# LIDO-HW_100_RearConnector.net
KiCad netlist of a schematic drawn in Altium Designer
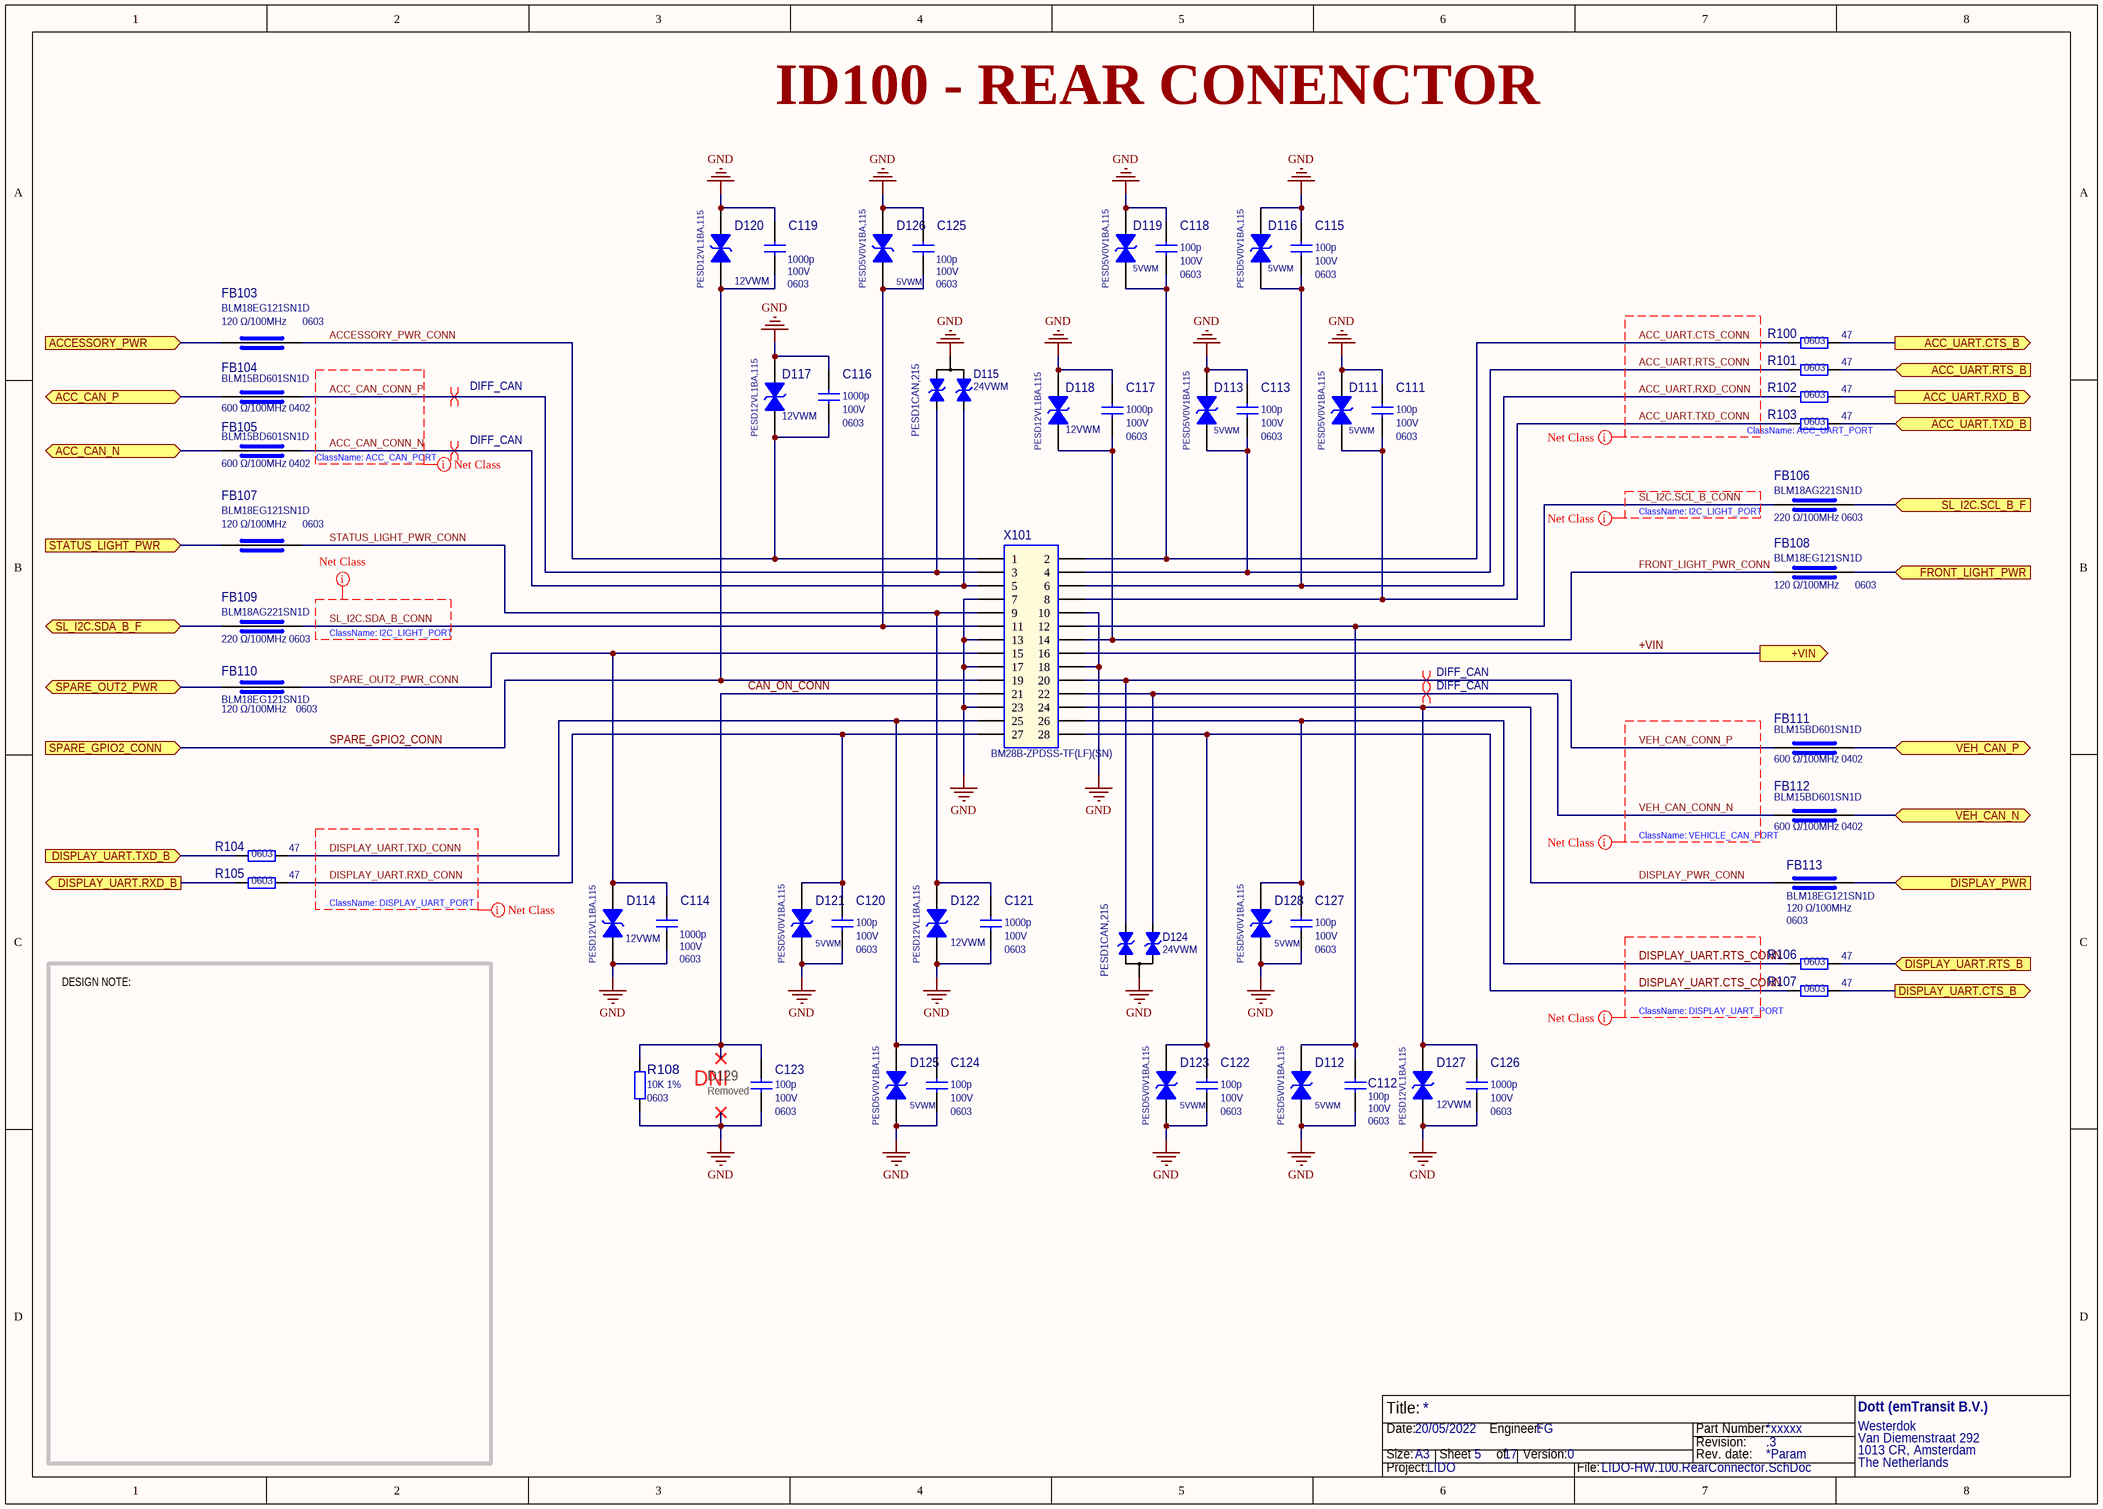
[diagram p0: LIDO-HW.100.RearConnector.SchDoc]

(export (version "E")
  (design (tool "Eeschema 10.0.6"))
  (components
    (comp (ref "C111")
      (value "100p")
      (footprint "CAP_0603_1608X90-N_MURATA_A")
      (description "CAP CER 100PF 100V C0G 0603")
      (fields
        (field (name "MANUFACTURER PART NUMBER") "CGA3E2C0G2A101J080AA")
        (field (name "MANUFACTURER") "TDK Corporation")
        (field (name "PART VALUE") "100p")
        (field (name "PART VALUE 2") "100V")
        (field (name "PART PACKAGE") "0603")
      )
      (libsource (lib "DB_Library") (part "Ceramic"))
    )
    (comp (ref "C112")
      (value "100p")
      (footprint "CAP_0603_1608X90-N_MURATA_A")
      (description "CAP CER 100PF 100V C0G 0603")
      (fields
        (field (name "MANUFACTURER PART NUMBER") "CGA3E2C0G2A101J080AA")
        (field (name "MANUFACTURER") "TDK Corporation")
        (field (name "PART VALUE") "100p")
        (field (name "PART VALUE 2") "100V")
        (field (name "PART PACKAGE") "0603")
      )
      (libsource (lib "DB_Library") (part "Ceramic"))
    )
    (comp (ref "C113")
      (value "100p")
      (footprint "CAP_0603_1608X90-N_MURATA_A")
      (description "CAP CER 100PF 100V C0G 0603")
      (fields
        (field (name "MANUFACTURER PART NUMBER") "CGA3E2C0G2A101J080AA")
        (field (name "MANUFACTURER") "TDK Corporation")
        (field (name "PART VALUE") "100p")
        (field (name "PART VALUE 2") "100V")
        (field (name "PART PACKAGE") "0603")
      )
      (libsource (lib "DB_Library") (part "Ceramic"))
    )
    (comp (ref "C114")
      (value "1000p")
      (footprint "CAP_0603_1608X90-N_MURATA_A")
      (description "CAP CER 1000PF 100V X7R 0603")
      (fields
        (field (name "MANUFACTURER PART NUMBER") "CGA3E2X7R2A102K080AA")
        (field (name "MANUFACTURER") "TDK Corporation")
        (field (name "PART VALUE") "1000p")
        (field (name "PART VALUE 2") "100V")
        (field (name "PART PACKAGE") "0603")
      )
      (libsource (lib "DB_Library") (part "Ceramic"))
    )
    (comp (ref "C115")
      (value "100p")
      (footprint "CAP_0603_1608X90-N_MURATA_A")
      (description "CAP CER 100PF 100V C0G 0603")
      (fields
        (field (name "MANUFACTURER PART NUMBER") "CGA3E2C0G2A101J080AA")
        (field (name "MANUFACTURER") "TDK Corporation")
        (field (name "PART VALUE") "100p")
        (field (name "PART VALUE 2") "100V")
        (field (name "PART PACKAGE") "0603")
      )
      (libsource (lib "DB_Library") (part "Ceramic"))
    )
    (comp (ref "C116")
      (value "1000p")
      (footprint "CAP_0603_1608X90-N_MURATA_A")
      (description "CAP CER 1000PF 100V X7R 0603")
      (fields
        (field (name "MANUFACTURER PART NUMBER") "CGA3E2X7R2A102K080AA")
        (field (name "MANUFACTURER") "TDK Corporation")
        (field (name "PART VALUE") "1000p")
        (field (name "PART VALUE 2") "100V")
        (field (name "PART PACKAGE") "0603")
      )
      (libsource (lib "DB_Library") (part "Ceramic"))
    )
    (comp (ref "C117")
      (value "1000p")
      (footprint "CAP_0603_1608X90-N_MURATA_A")
      (description "CAP CER 1000PF 100V X7R 0603")
      (fields
        (field (name "MANUFACTURER PART NUMBER") "CGA3E2X7R2A102K080AA")
        (field (name "MANUFACTURER") "TDK Corporation")
        (field (name "PART VALUE") "1000p")
        (field (name "PART VALUE 2") "100V")
        (field (name "PART PACKAGE") "0603")
      )
      (libsource (lib "DB_Library") (part "Ceramic"))
    )
    (comp (ref "C118")
      (value "100p")
      (footprint "CAP_0603_1608X90-N_MURATA_A")
      (description "CAP CER 100PF 100V C0G 0603")
      (fields
        (field (name "MANUFACTURER PART NUMBER") "CGA3E2C0G2A101J080AA")
        (field (name "MANUFACTURER") "TDK Corporation")
        (field (name "PART VALUE") "100p")
        (field (name "PART VALUE 2") "100V")
        (field (name "PART PACKAGE") "0603")
      )
      (libsource (lib "DB_Library") (part "Ceramic"))
    )
    (comp (ref "C119")
      (value "1000p")
      (footprint "CAP_0603_1608X90-N_MURATA_A")
      (description "CAP CER 1000PF 100V X7R 0603")
      (fields
        (field (name "MANUFACTURER PART NUMBER") "CGA3E2X7R2A102K080AA")
        (field (name "MANUFACTURER") "TDK Corporation")
        (field (name "PART VALUE") "1000p")
        (field (name "PART VALUE 2") "100V")
        (field (name "PART PACKAGE") "0603")
      )
      (libsource (lib "DB_Library") (part "Ceramic"))
    )
    (comp (ref "C120")
      (value "100p")
      (footprint "CAP_0603_1608X90-N_MURATA_A")
      (description "CAP CER 100PF 100V C0G 0603")
      (fields
        (field (name "MANUFACTURER PART NUMBER") "CGA3E2C0G2A101J080AA")
        (field (name "MANUFACTURER") "TDK Corporation")
        (field (name "PART VALUE") "100p")
        (field (name "PART VALUE 2") "100V")
        (field (name "PART PACKAGE") "0603")
      )
      (libsource (lib "DB_Library") (part "Ceramic"))
    )
    (comp (ref "C121")
      (value "1000p")
      (footprint "CAP_0603_1608X90-N_MURATA_A")
      (description "CAP CER 1000PF 100V X7R 0603")
      (fields
        (field (name "MANUFACTURER PART NUMBER") "CGA3E2X7R2A102K080AA")
        (field (name "MANUFACTURER") "TDK Corporation")
        (field (name "PART VALUE") "1000p")
        (field (name "PART VALUE 2") "100V")
        (field (name "PART PACKAGE") "0603")
      )
      (libsource (lib "DB_Library") (part "Ceramic"))
    )
    (comp (ref "C122")
      (value "100p")
      (footprint "CAP_0603_1608X90-N_MURATA_A")
      (description "CAP CER 100PF 100V C0G 0603")
      (fields
        (field (name "MANUFACTURER PART NUMBER") "CGA3E2C0G2A101J080AA")
        (field (name "MANUFACTURER") "TDK Corporation")
        (field (name "PART VALUE") "100p")
        (field (name "PART VALUE 2") "100V")
        (field (name "PART PACKAGE") "0603")
      )
      (libsource (lib "DB_Library") (part "Ceramic"))
    )
    (comp (ref "C123")
      (value "100p")
      (footprint "CAP_0603_1608X90-N_MURATA_A")
      (description "CAP CER 100PF 100V C0G 0603")
      (fields
        (field (name "MANUFACTURER PART NUMBER") "CGA3E2C0G2A101J080AA")
        (field (name "MANUFACTURER") "TDK Corporation")
        (field (name "PART VALUE") "100p")
        (field (name "PART VALUE 2") "100V")
        (field (name "PART PACKAGE") "0603")
      )
      (libsource (lib "DB_Library") (part "Ceramic"))
    )
    (comp (ref "C124")
      (value "100p")
      (footprint "CAP_0603_1608X90-N_MURATA_A")
      (description "CAP CER 100PF 100V C0G 0603")
      (fields
        (field (name "MANUFACTURER PART NUMBER") "CGA3E2C0G2A101J080AA")
        (field (name "MANUFACTURER") "TDK Corporation")
        (field (name "PART VALUE") "100p")
        (field (name "PART VALUE 2") "100V")
        (field (name "PART PACKAGE") "0603")
      )
      (libsource (lib "DB_Library") (part "Ceramic"))
    )
    (comp (ref "C125")
      (value "100p")
      (footprint "CAP_0603_1608X90-N_MURATA_A")
      (description "CAP CER 100PF 100V C0G 0603")
      (fields
        (field (name "MANUFACTURER PART NUMBER") "CGA3E2C0G2A101J080AA")
        (field (name "MANUFACTURER") "TDK Corporation")
        (field (name "PART VALUE") "100p")
        (field (name "PART VALUE 2") "100V")
        (field (name "PART PACKAGE") "0603")
      )
      (libsource (lib "DB_Library") (part "Ceramic"))
    )
    (comp (ref "C126")
      (value "1000p")
      (footprint "CAP_0603_1608X90-N_MURATA_A")
      (description "CAP CER 1000PF 100V X7R 0603")
      (fields
        (field (name "MANUFACTURER PART NUMBER") "CGA3E2X7R2A102K080AA")
        (field (name "MANUFACTURER") "TDK Corporation")
        (field (name "PART VALUE") "1000p")
        (field (name "PART VALUE 2") "100V")
        (field (name "PART PACKAGE") "0603")
      )
      (libsource (lib "DB_Library") (part "Ceramic"))
    )
    (comp (ref "C127")
      (value "100p")
      (footprint "CAP_0603_1608X90-N_MURATA_A")
      (description "CAP CER 100PF 100V C0G 0603")
      (fields
        (field (name "MANUFACTURER PART NUMBER") "CGA3E2C0G2A101J080AA")
        (field (name "MANUFACTURER") "TDK Corporation")
        (field (name "PART VALUE") "100p")
        (field (name "PART VALUE 2") "100V")
        (field (name "PART PACKAGE") "0603")
      )
      (libsource (lib "DB_Library") (part "Ceramic"))
    )
    (comp (ref "D111")
      (value "5VWM")
      (footprint "NXP_SOD-323_250X125X95L30x32_A")
      (description "12.5V Clamp 4.8A (8/20µs) Ipp Tvs Diode Surface Mount SOD-323")
      (fields
        (field (name "MANUFACTURER PART NUMBER") "PESD5V0V1BA,115")
        (field (name "MANUFACTURER") "Nexperia USA Inc.")
        (field (name "PART VALUE") "5VWM")
        (field (name "OBSOLETE PART") "False")
      )
      (libsource (lib "DB_Library") (part "BI-TVS_DIODE_B"))
    )
    (comp (ref "D112")
      (value "5VWM")
      (footprint "NXP_SOD-323_250X125X95L30x32_A")
      (description "12.5V Clamp 4.8A (8/20µs) Ipp Tvs Diode Surface Mount SOD-323")
      (fields
        (field (name "MANUFACTURER PART NUMBER") "PESD5V0V1BA,115")
        (field (name "MANUFACTURER") "Nexperia USA Inc.")
        (field (name "PART VALUE") "5VWM")
        (field (name "OBSOLETE PART") "False")
      )
      (libsource (lib "DB_Library") (part "BI-TVS_DIODE_B"))
    )
    (comp (ref "D113")
      (value "5VWM")
      (footprint "NXP_SOD-323_250X125X95L30x32_A")
      (description "12.5V Clamp 4.8A (8/20µs) Ipp Tvs Diode Surface Mount SOD-323")
      (fields
        (field (name "MANUFACTURER PART NUMBER") "PESD5V0V1BA,115")
        (field (name "MANUFACTURER") "Nexperia USA Inc.")
        (field (name "PART VALUE") "5VWM")
        (field (name "OBSOLETE PART") "False")
      )
      (libsource (lib "DB_Library") (part "BI-TVS_DIODE_B"))
    )
    (comp (ref "D114")
      (value "12VWM")
      (footprint "NXP_SOD-323_250X125X95L30x32_A")
      (description "37V Clamp 5A (8/20µs) Ipp Tvs Diode Surface Mount SOD-323")
      (fields
        (field (name "MANUFACTURER PART NUMBER") "PESD12VL1BA,115")
        (field (name "MANUFACTURER") "Nexperia USA Inc.")
        (field (name "PART VALUE") "12VWM")
        (field (name "OBSOLETE PART") "False")
      )
      (libsource (lib "DB_Library") (part "BI-TVS_DIODE_B"))
    )
    (comp (ref "D115")
      (value "24VWM")
      (footprint "SOT23-3P95_230X100L30-N_NEXPERIA_A")
      (description "70V Clamp 3A (8/20µs) Ipp Tvs Diode Surface Mount TO-236AB")
      (fields
        (field (name "MANUFACTURER PART NUMBER") "PESD1CAN,215")
        (field (name "MANUFACTURER") "Nexperia USA Inc.")
        (field (name "OBSOLETE PART") "False")
      )
      (libsource (lib "DB_Library") (part "DOUBLE_BI-TVS_DIODE_B"))
    )
    (comp (ref "D116")
      (value "5VWM")
      (footprint "NXP_SOD-323_250X125X95L30x32_A")
      (description "12.5V Clamp 4.8A (8/20µs) Ipp Tvs Diode Surface Mount SOD-323")
      (fields
        (field (name "MANUFACTURER PART NUMBER") "PESD5V0V1BA,115")
        (field (name "MANUFACTURER") "Nexperia USA Inc.")
        (field (name "PART VALUE") "5VWM")
        (field (name "OBSOLETE PART") "False")
      )
      (libsource (lib "DB_Library") (part "BI-TVS_DIODE_B"))
    )
    (comp (ref "D117")
      (value "12VWM")
      (footprint "NXP_SOD-323_250X125X95L30x32_A")
      (description "37V Clamp 5A (8/20µs) Ipp Tvs Diode Surface Mount SOD-323")
      (fields
        (field (name "MANUFACTURER PART NUMBER") "PESD12VL1BA,115")
        (field (name "MANUFACTURER") "Nexperia USA Inc.")
        (field (name "PART VALUE") "12VWM")
        (field (name "OBSOLETE PART") "False")
      )
      (libsource (lib "DB_Library") (part "BI-TVS_DIODE_B"))
    )
    (comp (ref "D118")
      (value "12VWM")
      (footprint "NXP_SOD-323_250X125X95L30x32_A")
      (description "37V Clamp 5A (8/20µs) Ipp Tvs Diode Surface Mount SOD-323")
      (fields
        (field (name "MANUFACTURER PART NUMBER") "PESD12VL1BA,115")
        (field (name "MANUFACTURER") "Nexperia USA Inc.")
        (field (name "PART VALUE") "12VWM")
        (field (name "OBSOLETE PART") "False")
      )
      (libsource (lib "DB_Library") (part "BI-TVS_DIODE_B"))
    )
    (comp (ref "D119")
      (value "5VWM")
      (footprint "NXP_SOD-323_250X125X95L30x32_A")
      (description "12.5V Clamp 4.8A (8/20µs) Ipp Tvs Diode Surface Mount SOD-323")
      (fields
        (field (name "MANUFACTURER PART NUMBER") "PESD5V0V1BA,115")
        (field (name "MANUFACTURER") "Nexperia USA Inc.")
        (field (name "PART VALUE") "5VWM")
        (field (name "OBSOLETE PART") "False")
      )
      (libsource (lib "DB_Library") (part "BI-TVS_DIODE_B"))
    )
    (comp (ref "D120")
      (value "12VWM")
      (footprint "NXP_SOD-323_250X125X95L30x32_A")
      (description "37V Clamp 5A (8/20µs) Ipp Tvs Diode Surface Mount SOD-323")
      (fields
        (field (name "MANUFACTURER PART NUMBER") "PESD12VL1BA,115")
        (field (name "MANUFACTURER") "Nexperia USA Inc.")
        (field (name "PART VALUE") "12VWM")
        (field (name "OBSOLETE PART") "False")
      )
      (libsource (lib "DB_Library") (part "BI-TVS_DIODE_B"))
    )
    (comp (ref "D121")
      (value "5VWM")
      (footprint "NXP_SOD-323_250X125X95L30x32_A")
      (description "12.5V Clamp 4.8A (8/20µs) Ipp Tvs Diode Surface Mount SOD-323")
      (fields
        (field (name "MANUFACTURER PART NUMBER") "PESD5V0V1BA,115")
        (field (name "MANUFACTURER") "Nexperia USA Inc.")
        (field (name "PART VALUE") "5VWM")
        (field (name "OBSOLETE PART") "False")
      )
      (libsource (lib "DB_Library") (part "BI-TVS_DIODE_B"))
    )
    (comp (ref "D122")
      (value "12VWM")
      (footprint "NXP_SOD-323_250X125X95L30x32_A")
      (description "37V Clamp 5A (8/20µs) Ipp Tvs Diode Surface Mount SOD-323")
      (fields
        (field (name "MANUFACTURER PART NUMBER") "PESD12VL1BA,115")
        (field (name "MANUFACTURER") "Nexperia USA Inc.")
        (field (name "PART VALUE") "12VWM")
        (field (name "OBSOLETE PART") "False")
      )
      (libsource (lib "DB_Library") (part "BI-TVS_DIODE_B"))
    )
    (comp (ref "D123")
      (value "5VWM")
      (footprint "NXP_SOD-323_250X125X95L30x32_A")
      (description "12.5V Clamp 4.8A (8/20µs) Ipp Tvs Diode Surface Mount SOD-323")
      (fields
        (field (name "MANUFACTURER PART NUMBER") "PESD5V0V1BA,115")
        (field (name "MANUFACTURER") "Nexperia USA Inc.")
        (field (name "PART VALUE") "5VWM")
        (field (name "OBSOLETE PART") "False")
      )
      (libsource (lib "DB_Library") (part "BI-TVS_DIODE_B"))
    )
    (comp (ref "D124")
      (value "24VWM")
      (footprint "SOT23-3P95_230X100L30-N_NEXPERIA_A")
      (description "70V Clamp 3A (8/20µs) Ipp Tvs Diode Surface Mount TO-236AB")
      (fields
        (field (name "MANUFACTURER PART NUMBER") "PESD1CAN,215")
        (field (name "MANUFACTURER") "Nexperia USA Inc.")
        (field (name "OBSOLETE PART") "False")
      )
      (libsource (lib "DB_Library") (part "DOUBLE_BI-TVS_DIODE_B"))
    )
    (comp (ref "D125")
      (value "5VWM")
      (footprint "NXP_SOD-323_250X125X95L30x32_A")
      (description "12.5V Clamp 4.8A (8/20µs) Ipp Tvs Diode Surface Mount SOD-323")
      (fields
        (field (name "MANUFACTURER PART NUMBER") "PESD5V0V1BA,115")
        (field (name "MANUFACTURER") "Nexperia USA Inc.")
        (field (name "PART VALUE") "5VWM")
        (field (name "OBSOLETE PART") "False")
      )
      (libsource (lib "DB_Library") (part "BI-TVS_DIODE_B"))
    )
    (comp (ref "D126")
      (value "5VWM")
      (footprint "NXP_SOD-323_250X125X95L30x32_A")
      (description "12.5V Clamp 4.8A (8/20µs) Ipp Tvs Diode Surface Mount SOD-323")
      (fields
        (field (name "MANUFACTURER PART NUMBER") "PESD5V0V1BA,115")
        (field (name "MANUFACTURER") "Nexperia USA Inc.")
        (field (name "PART VALUE") "5VWM")
        (field (name "OBSOLETE PART") "False")
      )
      (libsource (lib "DB_Library") (part "BI-TVS_DIODE_B"))
    )
    (comp (ref "D127")
      (value "12VWM")
      (footprint "NXP_SOD-323_250X125X95L30x32_A")
      (description "37V Clamp 5A (8/20µs) Ipp Tvs Diode Surface Mount SOD-323")
      (fields
        (field (name "MANUFACTURER PART NUMBER") "PESD12VL1BA,115")
        (field (name "MANUFACTURER") "Nexperia USA Inc.")
        (field (name "PART VALUE") "12VWM")
        (field (name "OBSOLETE PART") "False")
      )
      (libsource (lib "DB_Library") (part "BI-TVS_DIODE_B"))
    )
    (comp (ref "D128")
      (value "5VWM")
      (footprint "NXP_SOD-323_250X125X95L30x32_A")
      (description "12.5V Clamp 4.8A (8/20µs) Ipp Tvs Diode Surface Mount SOD-323")
      (fields
        (field (name "MANUFACTURER PART NUMBER") "PESD5V0V1BA,115")
        (field (name "MANUFACTURER") "Nexperia USA Inc.")
        (field (name "PART VALUE") "5VWM")
        (field (name "OBSOLETE PART") "False")
      )
      (libsource (lib "DB_Library") (part "BI-TVS_DIODE_B"))
    )
    (comp (ref "FB103")
      (value "120 Ω/100MHz")
      (footprint "IND_0603_1608X95-N_AVX_A")
      (description "FERRITE BEAD 120 OHM 0603 1LN")
      (fields
        (field (name "MANUFACTURER PART NUMBER") "BLM18EG121SN1D")
        (field (name "MANUFACTURER") "Murata Electronics")
        (field (name "PART VALUE") "120 Ω/100MHz")
        (field (name "PART PACKAGE") "0603")
        (field (name "OBSOLETE PART") "False")
      )
      (libsource (lib "DB_Library") (part "FERRITE_BEAD"))
    )
    (comp (ref "FB104")
      (value "600 Ω/100MHz")
      (footprint "IND_0402_1005X60-N_AVX_A")
      (description "FERRITE BEAD 600 OHM 0402 1LN")
      (fields
        (field (name "MANUFACTURER PART NUMBER") "BLM15BD601SN1D")
        (field (name "MANUFACTURER") "Murata Electronics")
        (field (name "PART VALUE") "600 Ω/100MHz")
        (field (name "PART PACKAGE") "0402")
        (field (name "OBSOLETE PART") "False")
      )
      (libsource (lib "DB_Library") (part "FERRITE_BEAD"))
    )
    (comp (ref "FB105")
      (value "600 Ω/100MHz")
      (footprint "IND_0402_1005X60-N_AVX_A")
      (description "FERRITE BEAD 600 OHM 0402 1LN")
      (fields
        (field (name "MANUFACTURER PART NUMBER") "BLM15BD601SN1D")
        (field (name "MANUFACTURER") "Murata Electronics")
        (field (name "PART VALUE") "600 Ω/100MHz")
        (field (name "PART PACKAGE") "0402")
        (field (name "OBSOLETE PART") "False")
      )
      (libsource (lib "DB_Library") (part "FERRITE_BEAD"))
    )
    (comp (ref "FB106")
      (value "220 Ω/100MHz")
      (footprint "IND_0603_1608X95-N_AVX_A")
      (description "FERRITE BEAD 220 OHM 0603 1LN")
      (fields
        (field (name "MANUFACTURER PART NUMBER") "BLM18AG221SN1D")
        (field (name "MANUFACTURER") "Murata Electronics")
        (field (name "PART VALUE") "220 Ω/100MHz")
        (field (name "PART PACKAGE") "0603")
        (field (name "OBSOLETE PART") "False")
      )
      (libsource (lib "DB_Library") (part "FERRITE_BEAD"))
    )
    (comp (ref "FB107")
      (value "120 Ω/100MHz")
      (footprint "IND_0603_1608X95-N_AVX_A")
      (description "FERRITE BEAD 120 OHM 0603 1LN")
      (fields
        (field (name "MANUFACTURER PART NUMBER") "BLM18EG121SN1D")
        (field (name "MANUFACTURER") "Murata Electronics")
        (field (name "PART VALUE") "120 Ω/100MHz")
        (field (name "PART PACKAGE") "0603")
        (field (name "OBSOLETE PART") "False")
      )
      (libsource (lib "DB_Library") (part "FERRITE_BEAD"))
    )
    (comp (ref "FB108")
      (value "120 Ω/100MHz")
      (footprint "IND_0603_1608X95-N_AVX_A")
      (description "FERRITE BEAD 120 OHM 0603 1LN")
      (fields
        (field (name "MANUFACTURER PART NUMBER") "BLM18EG121SN1D")
        (field (name "MANUFACTURER") "Murata Electronics")
        (field (name "PART VALUE") "120 Ω/100MHz")
        (field (name "PART PACKAGE") "0603")
        (field (name "OBSOLETE PART") "False")
      )
      (libsource (lib "DB_Library") (part "FERRITE_BEAD"))
    )
    (comp (ref "FB109")
      (value "220 Ω/100MHz")
      (footprint "IND_0603_1608X95-N_AVX_A")
      (description "FERRITE BEAD 220 OHM 0603 1LN")
      (fields
        (field (name "MANUFACTURER PART NUMBER") "BLM18AG221SN1D")
        (field (name "MANUFACTURER") "Murata Electronics")
        (field (name "PART VALUE") "220 Ω/100MHz")
        (field (name "PART PACKAGE") "0603")
        (field (name "OBSOLETE PART") "False")
      )
      (libsource (lib "DB_Library") (part "FERRITE_BEAD"))
    )
    (comp (ref "FB110")
      (value "120 Ω/100MHz")
      (footprint "IND_0603_1608X95-N_AVX_A")
      (description "FERRITE BEAD 120 OHM 0603 1LN")
      (fields
        (field (name "MANUFACTURER PART NUMBER") "BLM18EG121SN1D")
        (field (name "MANUFACTURER") "Murata Electronics")
        (field (name "PART VALUE") "120 Ω/100MHz")
        (field (name "PART PACKAGE") "0603")
        (field (name "OBSOLETE PART") "False")
      )
      (libsource (lib "DB_Library") (part "FERRITE_BEAD"))
    )
    (comp (ref "FB111")
      (value "600 Ω/100MHz")
      (footprint "IND_0402_1005X60-N_AVX_A")
      (description "FERRITE BEAD 600 OHM 0402 1LN")
      (fields
        (field (name "MANUFACTURER PART NUMBER") "BLM15BD601SN1D")
        (field (name "MANUFACTURER") "Murata Electronics")
        (field (name "PART VALUE") "600 Ω/100MHz")
        (field (name "PART PACKAGE") "0402")
        (field (name "OBSOLETE PART") "False")
      )
      (libsource (lib "DB_Library") (part "FERRITE_BEAD"))
    )
    (comp (ref "FB112")
      (value "600 Ω/100MHz")
      (footprint "IND_0402_1005X60-N_AVX_A")
      (description "FERRITE BEAD 600 OHM 0402 1LN")
      (fields
        (field (name "MANUFACTURER PART NUMBER") "BLM15BD601SN1D")
        (field (name "MANUFACTURER") "Murata Electronics")
        (field (name "PART VALUE") "600 Ω/100MHz")
        (field (name "PART PACKAGE") "0402")
        (field (name "OBSOLETE PART") "False")
      )
      (libsource (lib "DB_Library") (part "FERRITE_BEAD"))
    )
    (comp (ref "FB113")
      (value "120 Ω/100MHz")
      (footprint "IND_0603_1608X95-N_AVX_A")
      (description "FERRITE BEAD 120 OHM 0603 1LN")
      (fields
        (field (name "MANUFACTURER PART NUMBER") "BLM18EG121SN1D")
        (field (name "MANUFACTURER") "Murata Electronics")
        (field (name "PART VALUE") "120 Ω/100MHz")
        (field (name "PART PACKAGE") "0603")
        (field (name "OBSOLETE PART") "False")
      )
      (libsource (lib "DB_Library") (part "FERRITE_BEAD"))
    )
    (comp (ref "R100")
      (value "47")
      (footprint "RES_0603_1608X60-N_YAGEO_A")
      (description "RES SMD 47 OHM 5% 1/4W 0603")
      (fields
        (field (name "MANUFACTURER PART NUMBER") "ERJ-PA3J470V")
        (field (name "MANUFACTURER") "Panasonic Electronic Components")
        (field (name "PART PACKAGE") "0603")
      )
      (libsource (lib "DB_Library") (part "Resistor"))
    )
    (comp (ref "R101")
      (value "47")
      (footprint "RES_0603_1608X60-N_YAGEO_A")
      (description "RES SMD 47 OHM 5% 1/4W 0603")
      (fields
        (field (name "MANUFACTURER PART NUMBER") "ERJ-PA3J470V")
        (field (name "MANUFACTURER") "Panasonic Electronic Components")
        (field (name "PART PACKAGE") "0603")
      )
      (libsource (lib "DB_Library") (part "Resistor"))
    )
    (comp (ref "R102")
      (value "47")
      (footprint "RES_0603_1608X60-N_YAGEO_A")
      (description "RES SMD 47 OHM 5% 1/4W 0603")
      (fields
        (field (name "MANUFACTURER PART NUMBER") "ERJ-PA3J470V")
        (field (name "MANUFACTURER") "Panasonic Electronic Components")
        (field (name "PART PACKAGE") "0603")
      )
      (libsource (lib "DB_Library") (part "Resistor"))
    )
    (comp (ref "R103")
      (value "47")
      (footprint "RES_0603_1608X60-N_YAGEO_A")
      (description "RES SMD 47 OHM 5% 1/4W 0603")
      (fields
        (field (name "MANUFACTURER PART NUMBER") "ERJ-PA3J470V")
        (field (name "MANUFACTURER") "Panasonic Electronic Components")
        (field (name "PART PACKAGE") "0603")
      )
      (libsource (lib "DB_Library") (part "Resistor"))
    )
    (comp (ref "R104")
      (value "47")
      (footprint "RES_0603_1608X60-N_YAGEO_A")
      (description "RES SMD 47 OHM 5% 1/4W 0603")
      (fields
        (field (name "MANUFACTURER PART NUMBER") "ERJ-PA3J470V")
        (field (name "MANUFACTURER") "Panasonic Electronic Components")
        (field (name "PART PACKAGE") "0603")
      )
      (libsource (lib "DB_Library") (part "Resistor"))
    )
    (comp (ref "R105")
      (value "47")
      (footprint "RES_0603_1608X60-N_YAGEO_A")
      (description "RES SMD 47 OHM 5% 1/4W 0603")
      (fields
        (field (name "MANUFACTURER PART NUMBER") "ERJ-PA3J470V")
        (field (name "MANUFACTURER") "Panasonic Electronic Components")
        (field (name "PART PACKAGE") "0603")
      )
      (libsource (lib "DB_Library") (part "Resistor"))
    )
    (comp (ref "R106")
      (value "47")
      (footprint "RES_0603_1608X60-N_YAGEO_A")
      (description "RES SMD 47 OHM 5% 1/4W 0603")
      (fields
        (field (name "MANUFACTURER PART NUMBER") "ERJ-PA3J470V")
        (field (name "MANUFACTURER") "Panasonic Electronic Components")
        (field (name "PART PACKAGE") "0603")
      )
      (libsource (lib "DB_Library") (part "Resistor"))
    )
    (comp (ref "R107")
      (value "47")
      (footprint "RES_0603_1608X60-N_YAGEO_A")
      (description "RES SMD 47 OHM 5% 1/4W 0603")
      (fields
        (field (name "MANUFACTURER PART NUMBER") "ERJ-PA3J470V")
        (field (name "MANUFACTURER") "Panasonic Electronic Components")
        (field (name "PART PACKAGE") "0603")
      )
      (libsource (lib "DB_Library") (part "Resistor"))
    )
    (comp (ref "R108")
      (value "10K")
      (footprint "RES_0603_1608X60-N_YAGEO_A")
      (description "RES 10K OHM 1% 1/10W 0603")
      (fields
        (field (name "MANUFACTURER PART NUMBER") "RC0603FR-0710KL")
        (field (name "MANUFACTURER") "YAGEO")
        (field (name "PART VALUE") "10K")
        (field (name "PART VALUE 2") "1%")
        (field (name "PART PACKAGE") "0603")
      )
      (libsource (lib "") (part "Resistor_1"))
    )
    (comp (ref "X101")
      (value "BM28B-ZPDSS-TF(LF)(SN)")
      (footprint "JST_BM28B-ZPDSS-TF_A")
      (description "Connector Header Surface Mount 28 position 0.059\" (1.50mm)")
      (fields (field (name "MANUFACTURER") "JST Sales America Inc.") (field (name "OBSOLETE PART") "False"))
      (libsource (lib "DB_Library") (part "RECT_28PIN_2R_A"))
    )
  )
  (nets
    (net (code "1") (name "/+VIN") (class "Default")
      (node (ref "X101") (pin "16") (pinfunction "16_16") (pintype "passive"))
    )
    (net (code "2") (name "/ACCESSORY_PWR") (class "Default")
      (node (ref "FB103") (pin "1") (pinfunction "1_1") (pintype "passive"))
    )
    (net (code "3") (name "/ACCESSORY_PWR_CONN") (class "Default")
      (node (ref "C116") (pin "2") (pinfunction "2_2") (pintype "passive"))
      (node (ref "D117") (pin "C") (pinfunction "C_C") (pintype "passive"))
      (node (ref "FB103") (pin "2") (pinfunction "2_2") (pintype "passive"))
      (node (ref "X101") (pin "1") (pinfunction "1_1") (pintype "passive"))
    )
    (net (code "4") (name "/ACC_CAN_CONN_N") (class "Default")
      (node (ref "D115") (pin "1") (pinfunction "1_1") (pintype "passive"))
      (node (ref "FB105") (pin "2") (pinfunction "2_2") (pintype "passive"))
      (node (ref "X101") (pin "5") (pinfunction "5_5") (pintype "passive"))
    )
    (net (code "5") (name "/ACC_CAN_CONN_P") (class "Default")
      (node (ref "D115") (pin "2") (pinfunction "2_2") (pintype "passive"))
      (node (ref "FB104") (pin "2") (pinfunction "2_2") (pintype "passive"))
      (node (ref "X101") (pin "3") (pinfunction "3_3") (pintype "passive"))
    )
    (net (code "6") (name "/ACC_CAN_N") (class "Default")
      (node (ref "FB105") (pin "1") (pinfunction "1_1") (pintype "passive"))
    )
    (net (code "7") (name "/ACC_CAN_P") (class "Default")
      (node (ref "FB104") (pin "1") (pinfunction "1_1") (pintype "passive"))
    )
    (net (code "8") (name "/ACC_UART.CTS_B") (class "Default")
      (node (ref "R100") (pin "2") (pinfunction "2_2") (pintype "passive"))
    )
    (net (code "9") (name "/ACC_UART.CTS_CONN") (class "Default")
      (node (ref "C118") (pin "2") (pinfunction "2_2") (pintype "passive"))
      (node (ref "D119") (pin "C") (pinfunction "C_C") (pintype "passive"))
      (node (ref "R100") (pin "1") (pinfunction "1_1") (pintype "passive"))
      (node (ref "X101") (pin "2") (pinfunction "2_2") (pintype "passive"))
    )
    (net (code "10") (name "/ACC_UART.RTS_B") (class "Default")
      (node (ref "R101") (pin "2") (pinfunction "2_2") (pintype "passive"))
    )
    (net (code "11") (name "/ACC_UART.RTS_CONN") (class "Default")
      (node (ref "C113") (pin "2") (pinfunction "2_2") (pintype "passive"))
      (node (ref "D113") (pin "C") (pinfunction "C_C") (pintype "passive"))
      (node (ref "R101") (pin "1") (pinfunction "1_1") (pintype "passive"))
      (node (ref "X101") (pin "4") (pinfunction "4_4") (pintype "passive"))
    )
    (net (code "12") (name "/ACC_UART.RXD_B") (class "Default")
      (node (ref "R102") (pin "2") (pinfunction "2_2") (pintype "passive"))
    )
    (net (code "13") (name "/ACC_UART.RXD_CONN") (class "Default")
      (node (ref "C115") (pin "2") (pinfunction "2_2") (pintype "passive"))
      (node (ref "D116") (pin "C") (pinfunction "C_C") (pintype "passive"))
      (node (ref "R102") (pin "1") (pinfunction "1_1") (pintype "passive"))
      (node (ref "X101") (pin "6") (pinfunction "6_6") (pintype "passive"))
    )
    (net (code "14") (name "/ACC_UART.TXD_B") (class "Default")
      (node (ref "R103") (pin "2") (pinfunction "2_2") (pintype "passive"))
    )
    (net (code "15") (name "/ACC_UART.TXD_CONN") (class "Default")
      (node (ref "C111") (pin "2") (pinfunction "2_2") (pintype "passive"))
      (node (ref "D111") (pin "C") (pinfunction "C_C") (pintype "passive"))
      (node (ref "R103") (pin "1") (pinfunction "1_1") (pintype "passive"))
      (node (ref "X101") (pin "8") (pinfunction "8_8") (pintype "passive"))
    )
    (net (code "16") (name "/CAN_ON_CONN") (class "Default")
      (node (ref "C123") (pin "1") (pinfunction "1_1") (pintype "passive"))
      (node (ref "R108") (pin "2") (pinfunction "2_2") (pintype "passive"))
      (node (ref "X101") (pin "21") (pinfunction "21_21") (pintype "passive"))
    )
    (net (code "17") (name "/DISPLAY_PWR") (class "Default")
      (node (ref "FB113") (pin "2") (pinfunction "2_2") (pintype "passive"))
    )
    (net (code "18") (name "/DISPLAY_PWR_CONN") (class "Default")
      (node (ref "C126") (pin "1") (pinfunction "1_1") (pintype "passive"))
      (node (ref "D127") (pin "C") (pinfunction "C_C") (pintype "passive"))
      (node (ref "FB113") (pin "1") (pinfunction "1_1") (pintype "passive"))
      (node (ref "X101") (pin "24") (pinfunction "24_24") (pintype "passive"))
    )
    (net (code "19") (name "/DISPLAY_UART.CTS_B") (class "Default")
      (node (ref "R107") (pin "2") (pinfunction "2_2") (pintype "passive"))
    )
    (net (code "20") (name "/DISPLAY_UART.CTS_CONN") (class "Default")
      (node (ref "C122") (pin "1") (pinfunction "1_1") (pintype "passive"))
      (node (ref "D123") (pin "C") (pinfunction "C_C") (pintype "passive"))
      (node (ref "R107") (pin "1") (pinfunction "1_1") (pintype "passive"))
      (node (ref "X101") (pin "28") (pinfunction "28_28") (pintype "passive"))
    )
    (net (code "21") (name "/DISPLAY_UART.RTS_B") (class "Default")
      (node (ref "R106") (pin "2") (pinfunction "2_2") (pintype "passive"))
    )
    (net (code "22") (name "/DISPLAY_UART.RTS_CONN") (class "Default")
      (node (ref "C127") (pin "1") (pinfunction "1_1") (pintype "passive"))
      (node (ref "D128") (pin "C") (pinfunction "C_C") (pintype "passive"))
      (node (ref "R106") (pin "1") (pinfunction "1_1") (pintype "passive"))
      (node (ref "X101") (pin "26") (pinfunction "26_26") (pintype "passive"))
    )
    (net (code "23") (name "/DISPLAY_UART.RXD_B") (class "Default")
      (node (ref "R105") (pin "1") (pinfunction "1_1") (pintype "passive"))
    )
    (net (code "24") (name "/DISPLAY_UART.RXD_CONN") (class "Default")
      (node (ref "C120") (pin "1") (pinfunction "1_1") (pintype "passive"))
      (node (ref "D121") (pin "C") (pinfunction "C_C") (pintype "passive"))
      (node (ref "R105") (pin "2") (pinfunction "2_2") (pintype "passive"))
      (node (ref "X101") (pin "27") (pinfunction "27_27") (pintype "passive"))
    )
    (net (code "25") (name "/DISPLAY_UART.TXD_B") (class "Default")
      (node (ref "R104") (pin "1") (pinfunction "1_1") (pintype "passive"))
    )
    (net (code "26") (name "/DISPLAY_UART.TXD_CONN") (class "Default")
      (node (ref "C124") (pin "1") (pinfunction "1_1") (pintype "passive"))
      (node (ref "D125") (pin "C") (pinfunction "C_C") (pintype "passive"))
      (node (ref "R104") (pin "2") (pinfunction "2_2") (pintype "passive"))
      (node (ref "X101") (pin "25") (pinfunction "25_25") (pintype "passive"))
    )
    (net (code "27") (name "/FRONT_LIGHT_PWR") (class "Default")
      (node (ref "FB108") (pin "2") (pinfunction "2_2") (pintype "passive"))
    )
    (net (code "28") (name "/FRONT_LIGHT_PWR_CONN") (class "Default")
      (node (ref "C117") (pin "2") (pinfunction "2_2") (pintype "passive"))
      (node (ref "D118") (pin "C") (pinfunction "C_C") (pintype "passive"))
      (node (ref "FB108") (pin "1") (pinfunction "1_1") (pintype "passive"))
      (node (ref "X101") (pin "14") (pinfunction "14_14") (pintype "passive"))
    )
    (net (code "29") (name "/SL_I2C.SCL_B_CONN") (class "Default")
      (node (ref "C112") (pin "2") (pinfunction "2_2") (pintype "passive"))
      (node (ref "D112") (pin "C") (pinfunction "C_C") (pintype "passive"))
      (node (ref "FB106") (pin "1") (pinfunction "1_1") (pintype "passive"))
      (node (ref "X101") (pin "12") (pinfunction "12_12") (pintype "passive"))
    )
    (net (code "30") (name "/SL_I2C.SCL_B_F") (class "Default")
      (node (ref "FB106") (pin "2") (pinfunction "2_2") (pintype "passive"))
    )
    (net (code "31") (name "/SL_I2C.SDA_B_CONN") (class "Default")
      (node (ref "C125") (pin "1") (pinfunction "1_1") (pintype "passive"))
      (node (ref "D126") (pin "C") (pinfunction "C_C") (pintype "passive"))
      (node (ref "FB109") (pin "2") (pinfunction "2_2") (pintype "passive"))
      (node (ref "X101") (pin "11") (pinfunction "11_11") (pintype "passive"))
    )
    (net (code "32") (name "/SL_I2C.SDA_B_F") (class "Default")
      (node (ref "FB109") (pin "1") (pinfunction "1_1") (pintype "passive"))
    )
    (net (code "33") (name "/SPARE_GPIO2_CONN") (class "Default")
      (node (ref "C119") (pin "1") (pinfunction "1_1") (pintype "passive"))
      (node (ref "D120") (pin "C") (pinfunction "C_C") (pintype "passive"))
      (node (ref "X101") (pin "19") (pinfunction "19_19") (pintype "passive"))
    )
    (net (code "34") (name "/SPARE_OUT2_PWR") (class "Default")
      (node (ref "FB110") (pin "1") (pinfunction "1_1") (pintype "passive"))
    )
    (net (code "35") (name "/SPARE_OUT2_PWR_CONN") (class "Default")
      (node (ref "C114") (pin "2") (pinfunction "2_2") (pintype "passive"))
      (node (ref "D114") (pin "C") (pinfunction "C_C") (pintype "passive"))
      (node (ref "FB110") (pin "2") (pinfunction "2_2") (pintype "passive"))
      (node (ref "X101") (pin "15") (pinfunction "15_15") (pintype "passive"))
    )
    (net (code "36") (name "/STATUS_LIGHT_PWR") (class "Default")
      (node (ref "FB107") (pin "1") (pinfunction "1_1") (pintype "passive"))
    )
    (net (code "37") (name "/STATUS_LIGHT_PWR_CONN") (class "Default")
      (node (ref "C121") (pin "1") (pinfunction "1_1") (pintype "passive"))
      (node (ref "D122") (pin "C") (pinfunction "C_C") (pintype "passive"))
      (node (ref "FB107") (pin "2") (pinfunction "2_2") (pintype "passive"))
      (node (ref "X101") (pin "9") (pinfunction "9_9") (pintype "passive"))
    )
    (net (code "38") (name "/VEH_CAN_CONN_N") (class "Default")
      (node (ref "D124") (pin "2") (pinfunction "2_2") (pintype "passive"))
      (node (ref "FB112") (pin "1") (pinfunction "1_1") (pintype "passive"))
      (node (ref "X101") (pin "22") (pinfunction "22_22") (pintype "passive"))
    )
    (net (code "39") (name "/VEH_CAN_CONN_P") (class "Default")
      (node (ref "D124") (pin "1") (pinfunction "1_1") (pintype "passive"))
      (node (ref "FB111") (pin "1") (pinfunction "1_1") (pintype "passive"))
      (node (ref "X101") (pin "20") (pinfunction "20_20") (pintype "passive"))
    )
    (net (code "40") (name "/VEH_CAN_N") (class "Default")
      (node (ref "FB112") (pin "2") (pinfunction "2_2") (pintype "passive"))
    )
    (net (code "41") (name "/VEH_CAN_P") (class "Default")
      (node (ref "FB111") (pin "2") (pinfunction "2_2") (pintype "passive"))
    )
    (net (code "42") (name "GND") (class "Default")
      (node (ref "C111") (pin "1") (pinfunction "1_1") (pintype "passive"))
      (node (ref "C112") (pin "1") (pinfunction "1_1") (pintype "passive"))
      (node (ref "C113") (pin "1") (pinfunction "1_1") (pintype "passive"))
      (node (ref "C114") (pin "1") (pinfunction "1_1") (pintype "passive"))
      (node (ref "C115") (pin "1") (pinfunction "1_1") (pintype "passive"))
      (node (ref "C116") (pin "1") (pinfunction "1_1") (pintype "passive"))
      (node (ref "C117") (pin "1") (pinfunction "1_1") (pintype "passive"))
      (node (ref "C118") (pin "1") (pinfunction "1_1") (pintype "passive"))
      (node (ref "C119") (pin "2") (pinfunction "2_2") (pintype "passive"))
      (node (ref "C120") (pin "2") (pinfunction "2_2") (pintype "passive"))
      (node (ref "C121") (pin "2") (pinfunction "2_2") (pintype "passive"))
      (node (ref "C122") (pin "2") (pinfunction "2_2") (pintype "passive"))
      (node (ref "C123") (pin "2") (pinfunction "2_2") (pintype "passive"))
      (node (ref "C124") (pin "2") (pinfunction "2_2") (pintype "passive"))
      (node (ref "C125") (pin "2") (pinfunction "2_2") (pintype "passive"))
      (node (ref "C126") (pin "2") (pinfunction "2_2") (pintype "passive"))
      (node (ref "C127") (pin "2") (pinfunction "2_2") (pintype "passive"))
      (node (ref "D111") (pin "A") (pinfunction "A_A") (pintype "passive"))
      (node (ref "D112") (pin "A") (pinfunction "A_A") (pintype "passive"))
      (node (ref "D113") (pin "A") (pinfunction "A_A") (pintype "passive"))
      (node (ref "D114") (pin "A") (pinfunction "A_A") (pintype "passive"))
      (node (ref "D115") (pin "3") (pinfunction "3_3") (pintype "passive"))
      (node (ref "D116") (pin "A") (pinfunction "A_A") (pintype "passive"))
      (node (ref "D117") (pin "A") (pinfunction "A_A") (pintype "passive"))
      (node (ref "D118") (pin "A") (pinfunction "A_A") (pintype "passive"))
      (node (ref "D119") (pin "A") (pinfunction "A_A") (pintype "passive"))
      (node (ref "D120") (pin "A") (pinfunction "A_A") (pintype "passive"))
      (node (ref "D121") (pin "A") (pinfunction "A_A") (pintype "passive"))
      (node (ref "D122") (pin "A") (pinfunction "A_A") (pintype "passive"))
      (node (ref "D123") (pin "A") (pinfunction "A_A") (pintype "passive"))
      (node (ref "D124") (pin "3") (pinfunction "3_3") (pintype "passive"))
      (node (ref "D125") (pin "A") (pinfunction "A_A") (pintype "passive"))
      (node (ref "D126") (pin "A") (pinfunction "A_A") (pintype "passive"))
      (node (ref "D127") (pin "A") (pinfunction "A_A") (pintype "passive"))
      (node (ref "D128") (pin "A") (pinfunction "A_A") (pintype "passive"))
      (node (ref "R108") (pin "1") (pinfunction "1_1") (pintype "passive"))
      (node (ref "X101") (pin "10") (pinfunction "10_10") (pintype "passive"))
      (node (ref "X101") (pin "13") (pinfunction "13_13") (pintype "passive"))
      (node (ref "X101") (pin "17") (pinfunction "17_17") (pintype "passive"))
      (node (ref "X101") (pin "18") (pinfunction "18_18") (pintype "passive"))
      (node (ref "X101") (pin "23") (pinfunction "23_23") (pintype "passive"))
      (node (ref "X101") (pin "7") (pinfunction "7_7") (pintype "passive"))
    )
  )
)
